# 05_Sensors.net
KiCad netlist of a schematic drawn in Altium Designer
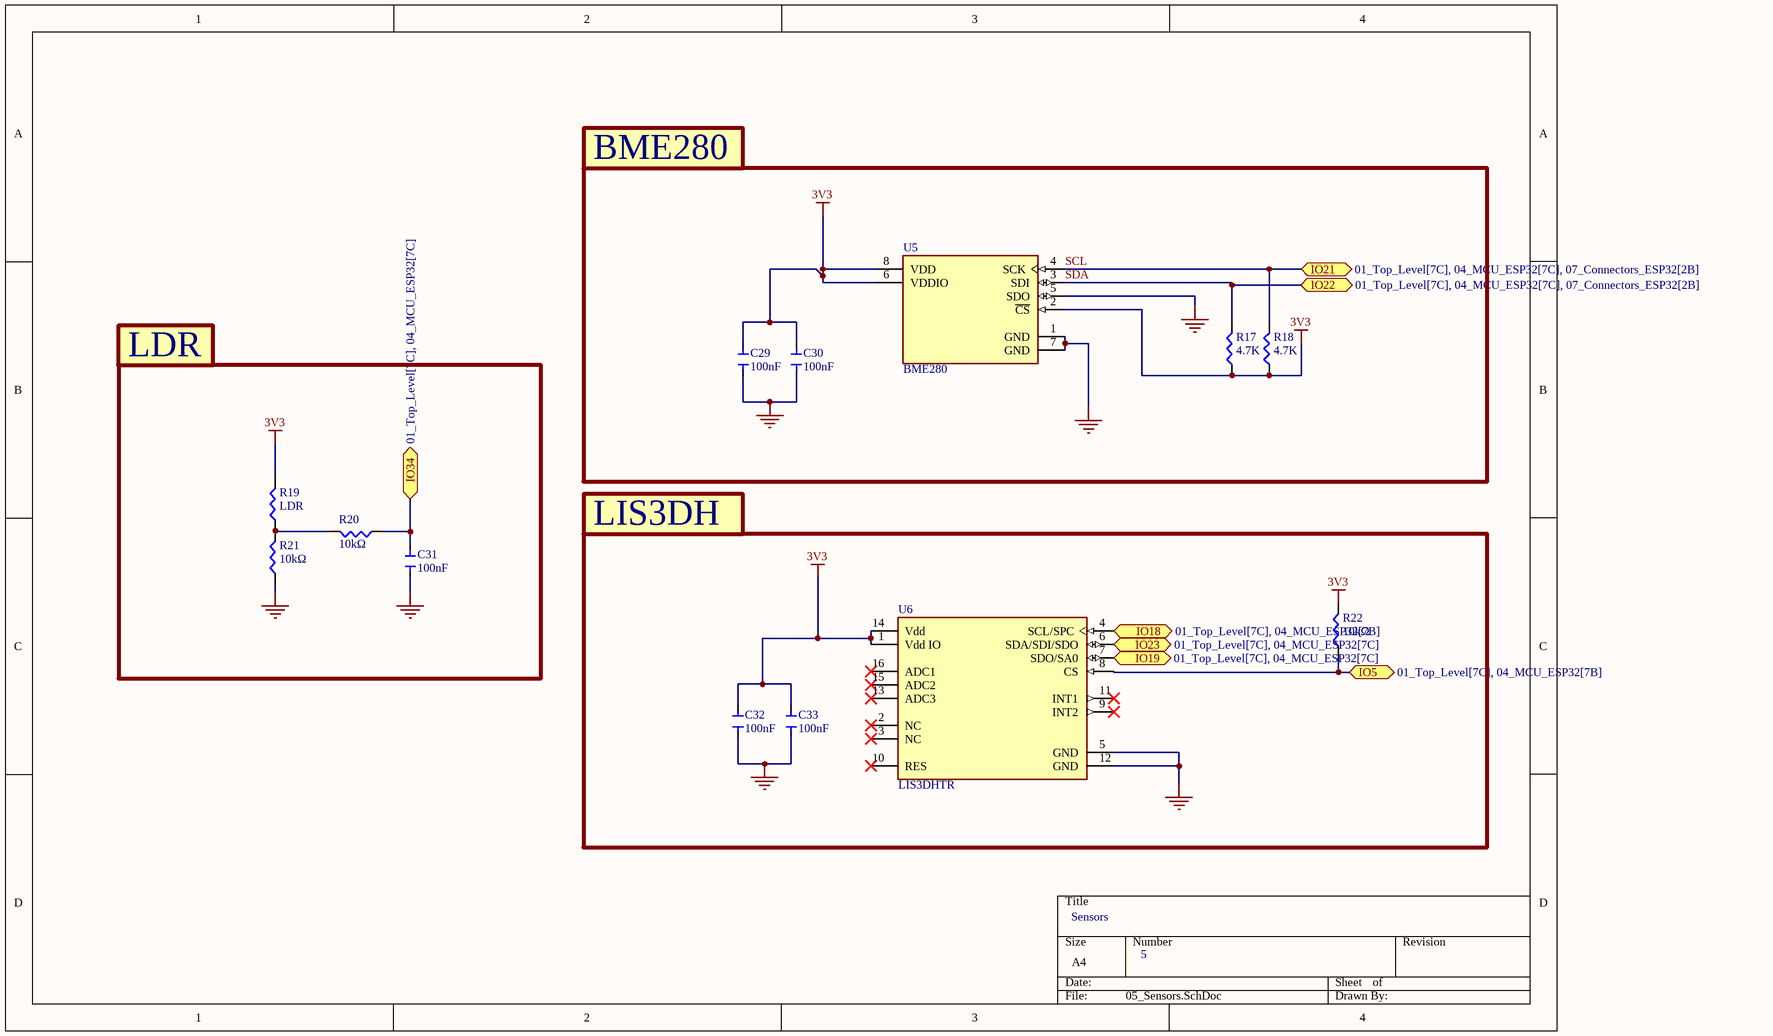
[diagram p0: 05_Sensors.SchDoc]

(export (version "E")
  (design (tool "Eeschema 10.0.6"))
  (components
    (comp (ref "C29")
      (value "100nF")
      (footprint "CAP_100nF")
      (description "CAP 100nF 50V X7R ±10% 0603 Ceramic Capacitors RoHS")
      (fields
        (field (name "MANUFACTURER") "YAGEO")
        (field (name "MANUFACTURER PART NUMBER") "CC0603KRX7R9BB104")
      )
      (libsource (lib "Components_Schlib") (part "CAP_100nF"))
    )
    (comp (ref "C30")
      (value "100nF")
      (footprint "CAP_100nF")
      (description "CAP 100nF 50V X7R ±10% 0603 Ceramic Capacitors RoHS")
      (fields
        (field (name "MANUFACTURER") "YAGEO")
        (field (name "MANUFACTURER PART NUMBER") "CC0603KRX7R9BB104")
      )
      (libsource (lib "Components_Schlib") (part "CAP_100nF"))
    )
    (comp (ref "C31")
      (value "100nF")
      (footprint "CAP_100nF")
      (description "CAP 100nF 50V X7R ±10% 0603 Ceramic Capacitors RoHS")
      (fields
        (field (name "MANUFACTURER") "YAGEO")
        (field (name "MANUFACTURER PART NUMBER") "CC0603KRX7R9BB104")
      )
      (libsource (lib "Components_Schlib") (part "CAP_100nF"))
    )
    (comp (ref "C32")
      (value "100nF")
      (footprint "CAP_100nF")
      (description "CAP 100nF 50V X7R ±10% 0603 Ceramic Capacitors RoHS")
      (fields
        (field (name "MANUFACTURER") "YAGEO")
        (field (name "MANUFACTURER PART NUMBER") "CC0603KRX7R9BB104")
      )
      (libsource (lib "Components_Schlib") (part "CAP_100nF"))
    )
    (comp (ref "C33")
      (value "100nF")
      (footprint "CAP_100nF")
      (description "CAP 100nF 50V X7R ±10% 0603 Ceramic Capacitors RoHS")
      (fields
        (field (name "MANUFACTURER") "YAGEO")
        (field (name "MANUFACTURER PART NUMBER") "CC0603KRX7R9BB104")
      )
      (libsource (lib "Components_Schlib") (part "CAP_100nF"))
    )
    (comp (ref "R17")
      (value "4.7K")
      (footprint "RES_2K")
      (description "100mW 2KΩ 75V Thick Film Resistor ±100ppm/℃ ±1% 0603 Chip Resistor - Surface Mount RoHS")
      (libsource (lib "Components_Schlib") (part "RSE_0603_2K"))
    )
    (comp (ref "R18")
      (value "4.7K")
      (footprint "RES_2K")
      (description "100mW 2KΩ 75V Thick Film Resistor ±100ppm/℃ ±1% 0603 Chip Resistor - Surface Mount RoHS")
      (libsource (lib "Components_Schlib") (part "RSE_0603_2K"))
    )
    (comp (ref "R19")
      (value "LDR")
      (footprint "RES_2K")
      (description "100mW 2KΩ 75V Thick Film Resistor ±100ppm/℃ ±1% 0603 Chip Resistor - Surface Mount RoHS")
      (libsource (lib "Components_Schlib") (part "RSE_0603_2K"))
    )
    (comp (ref "R20")
      (value "10kΩ")
      (footprint "RES_10K")
      (description "100mW Thin Film Resistor ±0.1% ±10ppm/℃ 10kΩ 0603 Chip Resistor - Surface Mount ROHS")
      (fields
        (field (name "MANUFACTURER") "Yageo Group")
        (field (name "MANUFACTURER PART NUMBER") "RT0603BRB07169KL")
      )
      (libsource (lib "Components_Schlib") (part "RES_0603_10K"))
    )
    (comp (ref "R21")
      (value "10kΩ")
      (footprint "RES_10K")
      (description "100mW Thin Film Resistor ±0.1% ±10ppm/℃ 10kΩ 0603 Chip Resistor - Surface Mount ROHS")
      (fields
        (field (name "MANUFACTURER") "Yageo Group")
        (field (name "MANUFACTURER PART NUMBER") "RT0603BRB07169KL")
      )
      (libsource (lib "Components_Schlib") (part "RES_0603_10K"))
    )
    (comp (ref "R22")
      (value "10kΩ")
      (footprint "RES_10K")
      (description "100mW Thin Film Resistor ±0.1% ±10ppm/℃ 10kΩ 0603 Chip Resistor - Surface Mount ROHS")
      (fields
        (field (name "MANUFACTURER") "Yageo Group")
        (field (name "MANUFACTURER PART NUMBER") "RT0603BRB07169KL")
      )
      (libsource (lib "Components_Schlib") (part "RES_0603_10K"))
    )
    (comp (ref "U5")
      (value "BME280")
      (footprint "FP-BME280-MFG")
      (description "SENSOR PRESSURE HUMIDITY TEMP")
      (libsource (lib "Altium Content Vault") (part "d58e2f6669bc67e6a2bc6a28610ca79"))
    )
    (comp (ref "U6")
      (value "LIS3DHTR")
      (footprint "FP-LGA-16-7983231-MFG")
      (description "ACCEL 2-16G I2C/SPI 16LGA")
      (libsource (lib "Altium Content Vault") (part "1e4772b22d749da4b53766bc623c8dd"))
    )
  )
  (nets
    (net (code "1") (name "/IO5") (class "Default")
      (node (ref "R22") (pin "1") (pinfunction "1_1") (pintype "passive"))
      (node (ref "U6") (pin "8") (pinfunction "CS_8") (pintype "input"))
    )
    (net (code "2") (name "/IO18") (class "Default")
      (node (ref "U6") (pin "4") (pinfunction "SCL/SPC_4") (pintype "input"))
    )
    (net (code "3") (name "/IO19") (class "Default")
      (node (ref "U6") (pin "7") (pinfunction "SDO/SA0_7") (pintype "bidirectional"))
    )
    (net (code "4") (name "/IO23") (class "Default")
      (node (ref "U6") (pin "6") (pinfunction "SDA/SDI/SDO_6") (pintype "bidirectional"))
    )
    (net (code "5") (name "/IO34") (class "Default")
      (node (ref "C31") (pin "2") (pinfunction "2_2") (pintype "passive"))
      (node (ref "R20") (pin "1") (pinfunction "1_1") (pintype "passive"))
    )
    (net (code "6") (name "/SCL") (class "Default")
      (node (ref "R18") (pin "2") (pinfunction "2_2") (pintype "passive"))
      (node (ref "U5") (pin "4") (pinfunction "SCK_4") (pintype "input"))
    )
    (net (code "7") (name "/SDA") (class "Default")
      (node (ref "R17") (pin "2") (pinfunction "2_2") (pintype "passive"))
      (node (ref "U5") (pin "3") (pinfunction "SDI_3") (pintype "bidirectional"))
    )
    (net (code "8") (name "3V3") (class "Default")
      (node (ref "C29") (pin "2") (pinfunction "2_2") (pintype "passive"))
      (node (ref "C30") (pin "2") (pinfunction "2_2") (pintype "passive"))
      (node (ref "C32") (pin "2") (pinfunction "2_2") (pintype "passive"))
      (node (ref "C33") (pin "2") (pinfunction "2_2") (pintype "passive"))
      (node (ref "R17") (pin "1") (pinfunction "1_1") (pintype "passive"))
      (node (ref "R18") (pin "1") (pinfunction "1_1") (pintype "passive"))
      (node (ref "R19") (pin "2") (pinfunction "2_2") (pintype "passive"))
      (node (ref "R22") (pin "2") (pinfunction "2_2") (pintype "passive"))
      (node (ref "U5") (pin "2") (pinfunction "~{CS}_2") (pintype "input"))
      (node (ref "U5") (pin "6") (pinfunction "VDDIO_6") (pintype "power_in"))
      (node (ref "U5") (pin "8") (pinfunction "VDD_8") (pintype "power_in"))
      (node (ref "U6") (pin "1") (pinfunction "Vdd_IO_1") (pintype "power_in"))
      (node (ref "U6") (pin "14") (pinfunction "Vdd_14") (pintype "power_in"))
    )
    (net (code "9") (name "GND") (class "Default")
      (node (ref "C29") (pin "1") (pinfunction "1_1") (pintype "passive"))
      (node (ref "C30") (pin "1") (pinfunction "1_1") (pintype "passive"))
      (node (ref "C31") (pin "1") (pinfunction "1_1") (pintype "passive"))
      (node (ref "C32") (pin "1") (pinfunction "1_1") (pintype "passive"))
      (node (ref "C33") (pin "1") (pinfunction "1_1") (pintype "passive"))
      (node (ref "R21") (pin "1") (pinfunction "1_1") (pintype "passive"))
      (node (ref "U5") (pin "1") (pinfunction "GND_1") (pintype "power_in"))
      (node (ref "U5") (pin "5") (pinfunction "SDO_5") (pintype "bidirectional"))
      (node (ref "U5") (pin "7") (pinfunction "GND_7") (pintype "power_in"))
      (node (ref "U6") (pin "12") (pinfunction "GND_12") (pintype "power_in"))
      (node (ref "U6") (pin "5") (pinfunction "GND_5") (pintype "power_in"))
    )
    (net (code "10") (name "Net-(R19-Pad1)") (class "Default")
      (node (ref "R19") (pin "1") (pinfunction "1_1") (pintype "passive"))
      (node (ref "R20") (pin "2") (pinfunction "2_2") (pintype "passive"))
      (node (ref "R21") (pin "2") (pinfunction "2_2") (pintype "passive"))
    )
    (net (code "11") (name "unconnected-(U6-ADC1-Pad16)") (class "Default")
      (node (ref "U6") (pin "16") (pinfunction "ADC1_16") (pintype "passive+no_connect"))
    )
    (net (code "12") (name "unconnected-(U6-ADC2-Pad15)") (class "Default")
      (node (ref "U6") (pin "15") (pinfunction "ADC2_15") (pintype "passive+no_connect"))
    )
    (net (code "13") (name "unconnected-(U6-ADC3-Pad13)") (class "Default")
      (node (ref "U6") (pin "13") (pinfunction "ADC3_13") (pintype "passive+no_connect"))
    )
    (net (code "14") (name "unconnected-(U6-INT1-Pad11)") (class "Default")
      (node (ref "U6") (pin "11") (pinfunction "INT1_11") (pintype "output+no_connect"))
    )
    (net (code "15") (name "unconnected-(U6-INT2-Pad9)") (class "Default")
      (node (ref "U6") (pin "9") (pinfunction "INT2_9") (pintype "output+no_connect"))
    )
    (net (code "16") (name "unconnected-(U6-NC-Pad2)") (class "Default")
      (node (ref "U6") (pin "2") (pinfunction "NC_2") (pintype "passive+no_connect"))
    )
    (net (code "17") (name "unconnected-(U6-NC-Pad3)") (class "Default")
      (node (ref "U6") (pin "3") (pinfunction "NC_3") (pintype "passive+no_connect"))
    )
    (net (code "18") (name "unconnected-(U6-RES-Pad10)") (class "Default")
      (node (ref "U6") (pin "10") (pinfunction "RES_10") (pintype "passive+no_connect"))
    )
  )
)
